# IO-shield.net
KiCad netlist of a schematic drawn in EAGLE
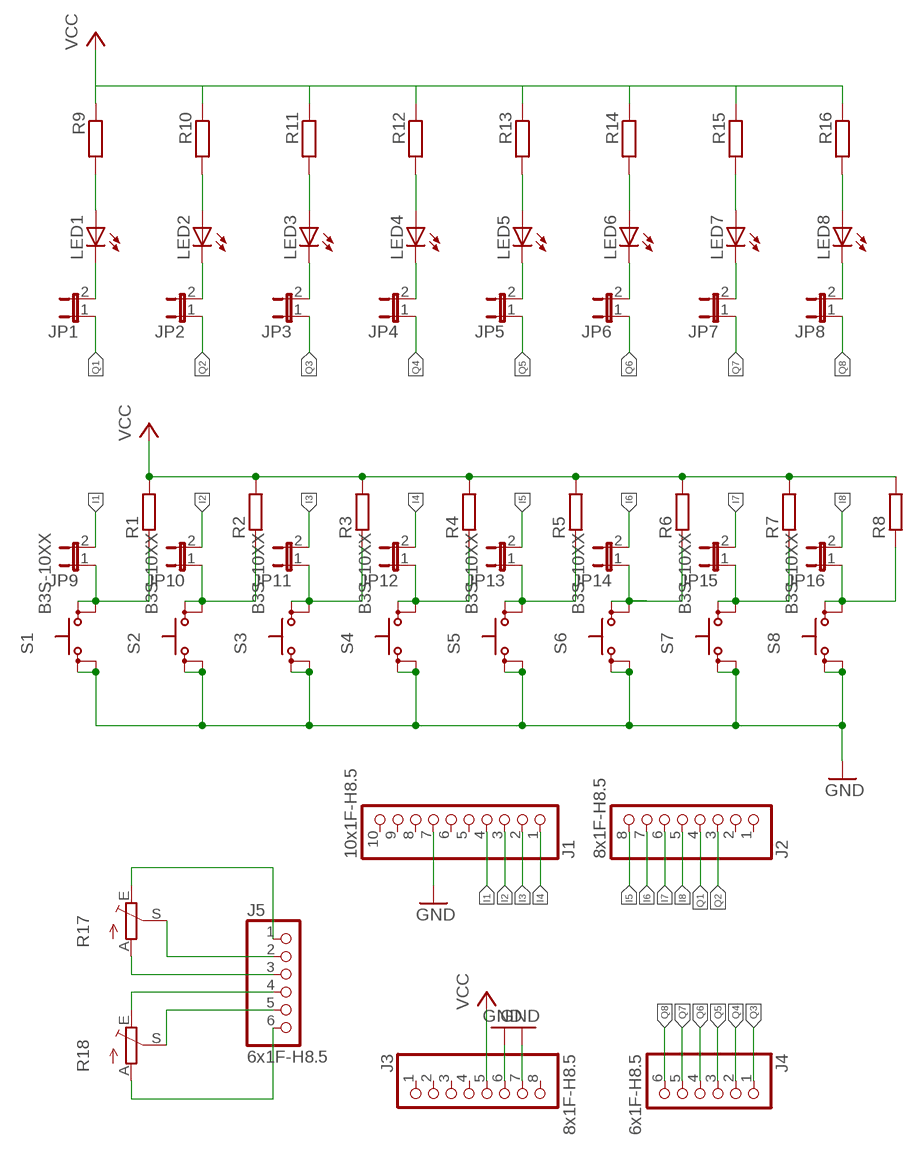
[diagram p0: schematic, sheet 1]

(export (version "E")
  (design (tool "Eeschema 10.0.6"))
  (components
    (comp (ref "J1")
      (value "10x1F-H8.5")
      (footprint "eagle-import:1X10")
      (libsource (lib "eagle-import") (part "PINHD-1X10"))
    )
    (comp (ref "J2")
      (value "8x1F-H8.5")
      (footprint "eagle-import:1X08")
      (libsource (lib "eagle-import") (part "PINHD-1X8"))
    )
    (comp (ref "J3")
      (value "8x1F-H8.5")
      (footprint "eagle-import:1X08")
      (libsource (lib "eagle-import") (part "PINHD-1X8"))
    )
    (comp (ref "J4")
      (value "6x1F-H8.5")
      (footprint "eagle-import:1X06")
      (libsource (lib "eagle-import") (part "PINHD-1X6"))
    )
    (comp (ref "J5")
      (value "6x1F-H8.5")
      (footprint "eagle-import:1X06")
      (libsource (lib "eagle-import") (part "PINHD-1X6"))
    )
    (comp (ref "JP1")
      (value "JP1E")
      (footprint "eagle-import:JP1")
      (libsource (lib "eagle-import") (part "JP1E"))
    )
    (comp (ref "JP2")
      (value "JP1E")
      (footprint "eagle-import:JP1")
      (libsource (lib "eagle-import") (part "JP1E"))
    )
    (comp (ref "JP3")
      (value "JP1E")
      (footprint "eagle-import:JP1")
      (libsource (lib "eagle-import") (part "JP1E"))
    )
    (comp (ref "JP4")
      (value "JP1E")
      (footprint "eagle-import:JP1")
      (libsource (lib "eagle-import") (part "JP1E"))
    )
    (comp (ref "JP5")
      (value "JP1E")
      (footprint "eagle-import:JP1")
      (libsource (lib "eagle-import") (part "JP1E"))
    )
    (comp (ref "JP6")
      (value "JP1E")
      (footprint "eagle-import:JP1")
      (libsource (lib "eagle-import") (part "JP1E"))
    )
    (comp (ref "JP7")
      (value "JP1E")
      (footprint "eagle-import:JP1")
      (libsource (lib "eagle-import") (part "JP1E"))
    )
    (comp (ref "JP8")
      (value "JP1E")
      (footprint "eagle-import:JP1")
      (libsource (lib "eagle-import") (part "JP1E"))
    )
    (comp (ref "JP9")
      (value "JP1E")
      (footprint "eagle-import:JP1")
      (libsource (lib "eagle-import") (part "JP1E"))
    )
    (comp (ref "JP10")
      (value "JP1E")
      (footprint "eagle-import:JP1")
      (libsource (lib "eagle-import") (part "JP1E"))
    )
    (comp (ref "JP11")
      (value "JP1E")
      (footprint "eagle-import:JP1")
      (libsource (lib "eagle-import") (part "JP1E"))
    )
    (comp (ref "JP12")
      (value "JP1E")
      (footprint "eagle-import:JP1")
      (libsource (lib "eagle-import") (part "JP1E"))
    )
    (comp (ref "JP13")
      (value "JP1E")
      (footprint "eagle-import:JP1")
      (libsource (lib "eagle-import") (part "JP1E"))
    )
    (comp (ref "JP14")
      (value "JP1E")
      (footprint "eagle-import:JP1")
      (libsource (lib "eagle-import") (part "JP1E"))
    )
    (comp (ref "JP15")
      (value "JP1E")
      (footprint "eagle-import:JP1")
      (libsource (lib "eagle-import") (part "JP1E"))
    )
    (comp (ref "JP16")
      (value "JP1E")
      (footprint "eagle-import:JP1")
      (libsource (lib "eagle-import") (part "JP1E"))
    )
    (comp (ref "LED1")
      (value "LEDKA-3528ASYC")
      (footprint "eagle-import:KA-3528ASYC")
      (libsource (lib "eagle-import") (part "LEDKA-3528ASYC"))
    )
    (comp (ref "LED2")
      (value "LEDKA-3528ASYC")
      (footprint "eagle-import:KA-3528ASYC")
      (libsource (lib "eagle-import") (part "LEDKA-3528ASYC"))
    )
    (comp (ref "LED3")
      (value "LEDKA-3528ASYC")
      (footprint "eagle-import:KA-3528ASYC")
      (libsource (lib "eagle-import") (part "LEDKA-3528ASYC"))
    )
    (comp (ref "LED4")
      (value "LEDKA-3528ASYC")
      (footprint "eagle-import:KA-3528ASYC")
      (libsource (lib "eagle-import") (part "LEDKA-3528ASYC"))
    )
    (comp (ref "LED5")
      (value "LEDKA-3528ASYC")
      (footprint "eagle-import:KA-3528ASYC")
      (libsource (lib "eagle-import") (part "LEDKA-3528ASYC"))
    )
    (comp (ref "LED6")
      (value "LEDKA-3528ASYC")
      (footprint "eagle-import:KA-3528ASYC")
      (libsource (lib "eagle-import") (part "LEDKA-3528ASYC"))
    )
    (comp (ref "LED7")
      (value "LEDKA-3528ASYC")
      (footprint "eagle-import:KA-3528ASYC")
      (libsource (lib "eagle-import") (part "LEDKA-3528ASYC"))
    )
    (comp (ref "LED8")
      (value "LEDKA-3528ASYC")
      (footprint "eagle-import:KA-3528ASYC")
      (libsource (lib "eagle-import") (part "LEDKA-3528ASYC"))
    )
    (comp (ref "R1")
      (value "R-EU_M1206")
      (footprint "eagle-import:M1206")
      (libsource (lib "eagle-import") (part "R-EU_M1206"))
    )
    (comp (ref "R2")
      (value "R-EU_M1206")
      (footprint "eagle-import:M1206")
      (libsource (lib "eagle-import") (part "R-EU_M1206"))
    )
    (comp (ref "R3")
      (value "R-EU_M1206")
      (footprint "eagle-import:M1206")
      (libsource (lib "eagle-import") (part "R-EU_M1206"))
    )
    (comp (ref "R4")
      (value "R-EU_M1206")
      (footprint "eagle-import:M1206")
      (libsource (lib "eagle-import") (part "R-EU_M1206"))
    )
    (comp (ref "R5")
      (value "R-EU_M1206")
      (footprint "eagle-import:M1206")
      (libsource (lib "eagle-import") (part "R-EU_M1206"))
    )
    (comp (ref "R6")
      (value "R-EU_M1206")
      (footprint "eagle-import:M1206")
      (libsource (lib "eagle-import") (part "R-EU_M1206"))
    )
    (comp (ref "R7")
      (value "R-EU_M1206")
      (footprint "eagle-import:M1206")
      (libsource (lib "eagle-import") (part "R-EU_M1206"))
    )
    (comp (ref "R8")
      (value "R-EU_M1206")
      (footprint "eagle-import:M1206")
      (libsource (lib "eagle-import") (part "R-EU_M1206"))
    )
    (comp (ref "R9")
      (value "R-EU_M1206")
      (footprint "eagle-import:M1206")
      (libsource (lib "eagle-import") (part "R-EU_M1206"))
    )
    (comp (ref "R10")
      (value "R-EU_M1206")
      (footprint "eagle-import:M1206")
      (libsource (lib "eagle-import") (part "R-EU_M1206"))
    )
    (comp (ref "R11")
      (value "R-EU_M1206")
      (footprint "eagle-import:M1206")
      (libsource (lib "eagle-import") (part "R-EU_M1206"))
    )
    (comp (ref "R12")
      (value "R-EU_M1206")
      (footprint "eagle-import:M1206")
      (libsource (lib "eagle-import") (part "R-EU_M1206"))
    )
    (comp (ref "R13")
      (value "R-EU_M1206")
      (footprint "eagle-import:M1206")
      (libsource (lib "eagle-import") (part "R-EU_M1206"))
    )
    (comp (ref "R14")
      (value "R-EU_M1206")
      (footprint "eagle-import:M1206")
      (libsource (lib "eagle-import") (part "R-EU_M1206"))
    )
    (comp (ref "R15")
      (value "R-EU_M1206")
      (footprint "eagle-import:M1206")
      (libsource (lib "eagle-import") (part "R-EU_M1206"))
    )
    (comp (ref "R16")
      (value "R-EU_M1206")
      (footprint "eagle-import:M1206")
      (libsource (lib "eagle-import") (part "R-EU_M1206"))
    )
    (comp (ref "R17")
      (value "TRIM_EU-CA6V")
      (footprint "eagle-import:CA6V")
      (libsource (lib "eagle-import") (part "TRIM_EU-CA6V"))
    )
    (comp (ref "R18")
      (value "TRIM_EU-CA6V")
      (footprint "eagle-import:CA6V")
      (libsource (lib "eagle-import") (part "TRIM_EU-CA6V"))
    )
    (comp (ref "S1")
      (value "B3S-10XX")
      (footprint "eagle-import:B3S-10XX")
      (libsource (lib "eagle-import") (part "B3S-10XX"))
    )
    (comp (ref "S2")
      (value "B3S-10XX")
      (footprint "eagle-import:B3S-10XX")
      (libsource (lib "eagle-import") (part "B3S-10XX"))
    )
    (comp (ref "S3")
      (value "B3S-10XX")
      (footprint "eagle-import:B3S-10XX")
      (libsource (lib "eagle-import") (part "B3S-10XX"))
    )
    (comp (ref "S4")
      (value "B3S-10XX")
      (footprint "eagle-import:B3S-10XX")
      (libsource (lib "eagle-import") (part "B3S-10XX"))
    )
    (comp (ref "S5")
      (value "B3S-10XX")
      (footprint "eagle-import:B3S-10XX")
      (libsource (lib "eagle-import") (part "B3S-10XX"))
    )
    (comp (ref "S6")
      (value "B3S-10XX")
      (footprint "eagle-import:B3S-10XX")
      (libsource (lib "eagle-import") (part "B3S-10XX"))
    )
    (comp (ref "S7")
      (value "B3S-10XX")
      (footprint "eagle-import:B3S-10XX")
      (libsource (lib "eagle-import") (part "B3S-10XX"))
    )
    (comp (ref "S8")
      (value "B3S-10XX")
      (footprint "eagle-import:B3S-10XX")
      (libsource (lib "eagle-import") (part "B3S-10XX"))
    )
  )
  (nets
    (net (code "1") (name "GND") (class "Default")
      (node (ref "J1") (pin "7") (pinfunction "7_7") (pintype "passive"))
      (node (ref "J3") (pin "6") (pinfunction "6_6") (pintype "passive"))
      (node (ref "J3") (pin "7") (pinfunction "7_7") (pintype "passive"))
      (node (ref "S1") (pin "1") (pinfunction "P_1") (pintype "passive"))
      (node (ref "S1") (pin "2") (pinfunction "P1_2") (pintype "passive"))
      (node (ref "S2") (pin "1") (pinfunction "P_1") (pintype "passive"))
      (node (ref "S2") (pin "2") (pinfunction "P1_2") (pintype "passive"))
      (node (ref "S3") (pin "1") (pinfunction "P_1") (pintype "passive"))
      (node (ref "S3") (pin "2") (pinfunction "P1_2") (pintype "passive"))
      (node (ref "S4") (pin "1") (pinfunction "P_1") (pintype "passive"))
      (node (ref "S4") (pin "2") (pinfunction "P1_2") (pintype "passive"))
      (node (ref "S5") (pin "1") (pinfunction "P_1") (pintype "passive"))
      (node (ref "S5") (pin "2") (pinfunction "P1_2") (pintype "passive"))
      (node (ref "S6") (pin "1") (pinfunction "P_1") (pintype "passive"))
      (node (ref "S6") (pin "2") (pinfunction "P1_2") (pintype "passive"))
      (node (ref "S7") (pin "1") (pinfunction "P_1") (pintype "passive"))
      (node (ref "S7") (pin "2") (pinfunction "P1_2") (pintype "passive"))
      (node (ref "S8") (pin "1") (pinfunction "P_1") (pintype "passive"))
      (node (ref "S8") (pin "2") (pinfunction "P1_2") (pintype "passive"))
    )
    (net (code "2") (name "I1") (class "Default")
      (node (ref "J1") (pin "4") (pinfunction "4_4") (pintype "passive"))
      (node (ref "JP9") (pin "2") (pinfunction "2_2") (pintype "passive"))
    )
    (net (code "3") (name "I2") (class "Default")
      (node (ref "J1") (pin "3") (pinfunction "3_3") (pintype "passive"))
      (node (ref "JP10") (pin "2") (pinfunction "2_2") (pintype "passive"))
    )
    (net (code "4") (name "I3") (class "Default")
      (node (ref "J1") (pin "2") (pinfunction "2_2") (pintype "passive"))
      (node (ref "JP11") (pin "2") (pinfunction "2_2") (pintype "passive"))
    )
    (net (code "5") (name "I4") (class "Default")
      (node (ref "J1") (pin "1") (pinfunction "1_1") (pintype "passive"))
      (node (ref "JP12") (pin "2") (pinfunction "2_2") (pintype "passive"))
    )
    (net (code "6") (name "I5") (class "Default")
      (node (ref "J2") (pin "8") (pinfunction "8_8") (pintype "passive"))
      (node (ref "JP13") (pin "2") (pinfunction "2_2") (pintype "passive"))
    )
    (net (code "7") (name "I6") (class "Default")
      (node (ref "J2") (pin "7") (pinfunction "7_7") (pintype "passive"))
      (node (ref "JP14") (pin "2") (pinfunction "2_2") (pintype "passive"))
    )
    (net (code "8") (name "I7") (class "Default")
      (node (ref "J2") (pin "6") (pinfunction "6_6") (pintype "passive"))
      (node (ref "JP15") (pin "2") (pinfunction "2_2") (pintype "passive"))
    )
    (net (code "9") (name "I8") (class "Default")
      (node (ref "J2") (pin "5") (pinfunction "5_5") (pintype "passive"))
      (node (ref "JP16") (pin "2") (pinfunction "2_2") (pintype "passive"))
    )
    (net (code "10") (name "Net-(J5-Pad1)") (class "Default")
      (node (ref "J5") (pin "1") (pinfunction "1_1") (pintype "passive"))
      (node (ref "R17") (pin "E") (pinfunction "E_E") (pintype "passive"))
    )
    (net (code "11") (name "Net-(J5-Pad2)") (class "Default")
      (node (ref "J5") (pin "2") (pinfunction "2_2") (pintype "passive"))
      (node (ref "R17") (pin "S") (pinfunction "S_S") (pintype "passive"))
    )
    (net (code "12") (name "Net-(J5-Pad3)") (class "Default")
      (node (ref "J5") (pin "3") (pinfunction "3_3") (pintype "passive"))
      (node (ref "R17") (pin "A") (pinfunction "A_A") (pintype "passive"))
    )
    (net (code "13") (name "Net-(J5-Pad4)") (class "Default")
      (node (ref "J5") (pin "4") (pinfunction "4_4") (pintype "passive"))
      (node (ref "R18") (pin "E") (pinfunction "E_E") (pintype "passive"))
    )
    (net (code "14") (name "Net-(J5-Pad5)") (class "Default")
      (node (ref "J5") (pin "5") (pinfunction "5_5") (pintype "passive"))
      (node (ref "R18") (pin "S") (pinfunction "S_S") (pintype "passive"))
    )
    (net (code "15") (name "Net-(J5-Pad6)") (class "Default")
      (node (ref "J5") (pin "6") (pinfunction "6_6") (pintype "passive"))
      (node (ref "R18") (pin "A") (pinfunction "A_A") (pintype "passive"))
    )
    (net (code "16") (name "Net-(JP1-Pad2)") (class "Default")
      (node (ref "JP1") (pin "2") (pinfunction "2_2") (pintype "passive"))
      (node (ref "LED1") (pin "C") (pinfunction "C_C") (pintype "passive"))
    )
    (net (code "17") (name "Net-(JP2-Pad2)") (class "Default")
      (node (ref "JP2") (pin "2") (pinfunction "2_2") (pintype "passive"))
      (node (ref "LED2") (pin "C") (pinfunction "C_C") (pintype "passive"))
    )
    (net (code "18") (name "Net-(JP3-Pad2)") (class "Default")
      (node (ref "JP3") (pin "2") (pinfunction "2_2") (pintype "passive"))
      (node (ref "LED3") (pin "C") (pinfunction "C_C") (pintype "passive"))
    )
    (net (code "19") (name "Net-(JP4-Pad2)") (class "Default")
      (node (ref "JP4") (pin "2") (pinfunction "2_2") (pintype "passive"))
      (node (ref "LED4") (pin "C") (pinfunction "C_C") (pintype "passive"))
    )
    (net (code "20") (name "Net-(JP5-Pad2)") (class "Default")
      (node (ref "JP5") (pin "2") (pinfunction "2_2") (pintype "passive"))
      (node (ref "LED5") (pin "C") (pinfunction "C_C") (pintype "passive"))
    )
    (net (code "21") (name "Net-(JP6-Pad2)") (class "Default")
      (node (ref "JP6") (pin "2") (pinfunction "2_2") (pintype "passive"))
      (node (ref "LED6") (pin "C") (pinfunction "C_C") (pintype "passive"))
    )
    (net (code "22") (name "Net-(JP7-Pad2)") (class "Default")
      (node (ref "JP7") (pin "2") (pinfunction "2_2") (pintype "passive"))
      (node (ref "LED7") (pin "C") (pinfunction "C_C") (pintype "passive"))
    )
    (net (code "23") (name "Net-(JP8-Pad2)") (class "Default")
      (node (ref "JP8") (pin "2") (pinfunction "2_2") (pintype "passive"))
      (node (ref "LED8") (pin "C") (pinfunction "C_C") (pintype "passive"))
    )
    (net (code "24") (name "Net-(LED1-PadA)") (class "Default")
      (node (ref "LED1") (pin "A") (pinfunction "A_A") (pintype "passive"))
      (node (ref "R9") (pin "2") (pinfunction "2_2") (pintype "passive"))
    )
    (net (code "25") (name "Net-(LED2-PadA)") (class "Default")
      (node (ref "LED2") (pin "A") (pinfunction "A_A") (pintype "passive"))
      (node (ref "R10") (pin "2") (pinfunction "2_2") (pintype "passive"))
    )
    (net (code "26") (name "Net-(LED3-PadA)") (class "Default")
      (node (ref "LED3") (pin "A") (pinfunction "A_A") (pintype "passive"))
      (node (ref "R11") (pin "2") (pinfunction "2_2") (pintype "passive"))
    )
    (net (code "27") (name "Net-(LED4-PadA)") (class "Default")
      (node (ref "LED4") (pin "A") (pinfunction "A_A") (pintype "passive"))
      (node (ref "R12") (pin "2") (pinfunction "2_2") (pintype "passive"))
    )
    (net (code "28") (name "Net-(LED5-PadA)") (class "Default")
      (node (ref "LED5") (pin "A") (pinfunction "A_A") (pintype "passive"))
      (node (ref "R13") (pin "2") (pinfunction "2_2") (pintype "passive"))
    )
    (net (code "29") (name "Net-(LED6-PadA)") (class "Default")
      (node (ref "LED6") (pin "A") (pinfunction "A_A") (pintype "passive"))
      (node (ref "R14") (pin "2") (pinfunction "2_2") (pintype "passive"))
    )
    (net (code "30") (name "Net-(LED7-PadA)") (class "Default")
      (node (ref "LED7") (pin "A") (pinfunction "A_A") (pintype "passive"))
      (node (ref "R15") (pin "2") (pinfunction "2_2") (pintype "passive"))
    )
    (net (code "31") (name "Net-(LED8-PadA)") (class "Default")
      (node (ref "LED8") (pin "A") (pinfunction "A_A") (pintype "passive"))
      (node (ref "R16") (pin "2") (pinfunction "2_2") (pintype "passive"))
    )
    (net (code "32") (name "Net-(S1-S)") (class "Default")
      (node (ref "JP9") (pin "1") (pinfunction "1_1") (pintype "passive"))
      (node (ref "R1") (pin "1") (pinfunction "1_1") (pintype "passive"))
      (node (ref "S1") (pin "3") (pinfunction "S_3") (pintype "passive"))
      (node (ref "S1") (pin "4") (pinfunction "S1_4") (pintype "passive"))
    )
    (net (code "33") (name "Net-(S2-S)") (class "Default")
      (node (ref "JP10") (pin "1") (pinfunction "1_1") (pintype "passive"))
      (node (ref "R2") (pin "1") (pinfunction "1_1") (pintype "passive"))
      (node (ref "S2") (pin "3") (pinfunction "S_3") (pintype "passive"))
      (node (ref "S2") (pin "4") (pinfunction "S1_4") (pintype "passive"))
    )
    (net (code "34") (name "Net-(S3-S)") (class "Default")
      (node (ref "JP11") (pin "1") (pinfunction "1_1") (pintype "passive"))
      (node (ref "R3") (pin "1") (pinfunction "1_1") (pintype "passive"))
      (node (ref "S3") (pin "3") (pinfunction "S_3") (pintype "passive"))
      (node (ref "S3") (pin "4") (pinfunction "S1_4") (pintype "passive"))
    )
    (net (code "35") (name "Net-(S4-S)") (class "Default")
      (node (ref "JP12") (pin "1") (pinfunction "1_1") (pintype "passive"))
      (node (ref "R4") (pin "1") (pinfunction "1_1") (pintype "passive"))
      (node (ref "S4") (pin "3") (pinfunction "S_3") (pintype "passive"))
      (node (ref "S4") (pin "4") (pinfunction "S1_4") (pintype "passive"))
    )
    (net (code "36") (name "Net-(S5-S)") (class "Default")
      (node (ref "JP13") (pin "1") (pinfunction "1_1") (pintype "passive"))
      (node (ref "R5") (pin "1") (pinfunction "1_1") (pintype "passive"))
      (node (ref "S5") (pin "3") (pinfunction "S_3") (pintype "passive"))
      (node (ref "S5") (pin "4") (pinfunction "S1_4") (pintype "passive"))
    )
    (net (code "37") (name "Net-(S6-S)") (class "Default")
      (node (ref "JP14") (pin "1") (pinfunction "1_1") (pintype "passive"))
      (node (ref "R6") (pin "1") (pinfunction "1_1") (pintype "passive"))
      (node (ref "S6") (pin "3") (pinfunction "S_3") (pintype "passive"))
      (node (ref "S6") (pin "4") (pinfunction "S1_4") (pintype "passive"))
    )
    (net (code "38") (name "Net-(S7-S)") (class "Default")
      (node (ref "JP15") (pin "1") (pinfunction "1_1") (pintype "passive"))
      (node (ref "R7") (pin "1") (pinfunction "1_1") (pintype "passive"))
      (node (ref "S7") (pin "3") (pinfunction "S_3") (pintype "passive"))
      (node (ref "S7") (pin "4") (pinfunction "S1_4") (pintype "passive"))
    )
    (net (code "39") (name "Net-(S8-S)") (class "Default")
      (node (ref "JP16") (pin "1") (pinfunction "1_1") (pintype "passive"))
      (node (ref "R8") (pin "1") (pinfunction "1_1") (pintype "passive"))
      (node (ref "S8") (pin "3") (pinfunction "S_3") (pintype "passive"))
      (node (ref "S8") (pin "4") (pinfunction "S1_4") (pintype "passive"))
    )
    (net (code "40") (name "Q1") (class "Default")
      (node (ref "J2") (pin "4") (pinfunction "4_4") (pintype "passive"))
      (node (ref "JP1") (pin "1") (pinfunction "1_1") (pintype "passive"))
    )
    (net (code "41") (name "Q2") (class "Default")
      (node (ref "J2") (pin "3") (pinfunction "3_3") (pintype "passive"))
      (node (ref "JP2") (pin "1") (pinfunction "1_1") (pintype "passive"))
    )
    (net (code "42") (name "Q3") (class "Default")
      (node (ref "J4") (pin "1") (pinfunction "1_1") (pintype "passive"))
      (node (ref "JP3") (pin "1") (pinfunction "1_1") (pintype "passive"))
    )
    (net (code "43") (name "Q4") (class "Default")
      (node (ref "J4") (pin "2") (pinfunction "2_2") (pintype "passive"))
      (node (ref "JP4") (pin "1") (pinfunction "1_1") (pintype "passive"))
    )
    (net (code "44") (name "Q5") (class "Default")
      (node (ref "J4") (pin "3") (pinfunction "3_3") (pintype "passive"))
      (node (ref "JP5") (pin "1") (pinfunction "1_1") (pintype "passive"))
    )
    (net (code "45") (name "Q6") (class "Default")
      (node (ref "J4") (pin "4") (pinfunction "4_4") (pintype "passive"))
      (node (ref "JP6") (pin "1") (pinfunction "1_1") (pintype "passive"))
    )
    (net (code "46") (name "Q7") (class "Default")
      (node (ref "J4") (pin "5") (pinfunction "5_5") (pintype "passive"))
      (node (ref "JP7") (pin "1") (pinfunction "1_1") (pintype "passive"))
    )
    (net (code "47") (name "Q8") (class "Default")
      (node (ref "J4") (pin "6") (pinfunction "6_6") (pintype "passive"))
      (node (ref "JP8") (pin "1") (pinfunction "1_1") (pintype "passive"))
    )
    (net (code "48") (name "VCC") (class "Default")
      (node (ref "J3") (pin "5") (pinfunction "5_5") (pintype "passive"))
      (node (ref "R1") (pin "2") (pinfunction "2_2") (pintype "passive"))
      (node (ref "R10") (pin "1") (pinfunction "1_1") (pintype "passive"))
      (node (ref "R11") (pin "1") (pinfunction "1_1") (pintype "passive"))
      (node (ref "R12") (pin "1") (pinfunction "1_1") (pintype "passive"))
      (node (ref "R13") (pin "1") (pinfunction "1_1") (pintype "passive"))
      (node (ref "R14") (pin "1") (pinfunction "1_1") (pintype "passive"))
      (node (ref "R15") (pin "1") (pinfunction "1_1") (pintype "passive"))
      (node (ref "R16") (pin "1") (pinfunction "1_1") (pintype "passive"))
      (node (ref "R2") (pin "2") (pinfunction "2_2") (pintype "passive"))
      (node (ref "R3") (pin "2") (pinfunction "2_2") (pintype "passive"))
      (node (ref "R4") (pin "2") (pinfunction "2_2") (pintype "passive"))
      (node (ref "R5") (pin "2") (pinfunction "2_2") (pintype "passive"))
      (node (ref "R6") (pin "2") (pinfunction "2_2") (pintype "passive"))
      (node (ref "R7") (pin "2") (pinfunction "2_2") (pintype "passive"))
      (node (ref "R8") (pin "2") (pinfunction "2_2") (pintype "passive"))
      (node (ref "R9") (pin "1") (pinfunction "1_1") (pintype "passive"))
    )
    (net (code "49") (name "unconnected-(J1-Pad5)") (class "Default")
      (node (ref "J1") (pin "5") (pinfunction "5_5") (pintype "passive"))
    )
    (net (code "50") (name "unconnected-(J1-Pad6)") (class "Default")
      (node (ref "J1") (pin "6") (pinfunction "6_6") (pintype "passive"))
    )
    (net (code "51") (name "unconnected-(J1-Pad8)") (class "Default")
      (node (ref "J1") (pin "8") (pinfunction "8_8") (pintype "passive"))
    )
    (net (code "52") (name "unconnected-(J1-Pad9)") (class "Default")
      (node (ref "J1") (pin "9") (pinfunction "9_9") (pintype "passive"))
    )
    (net (code "53") (name "unconnected-(J1-Pad10)") (class "Default")
      (node (ref "J1") (pin "10") (pinfunction "10_10") (pintype "passive"))
    )
    (net (code "54") (name "unconnected-(J2-Pad1)") (class "Default")
      (node (ref "J2") (pin "1") (pinfunction "1_1") (pintype "passive"))
    )
    (net (code "55") (name "unconnected-(J2-Pad2)") (class "Default")
      (node (ref "J2") (pin "2") (pinfunction "2_2") (pintype "passive"))
    )
    (net (code "56") (name "unconnected-(J3-Pad1)") (class "Default")
      (node (ref "J3") (pin "1") (pinfunction "1_1") (pintype "passive"))
    )
    (net (code "57") (name "unconnected-(J3-Pad2)") (class "Default")
      (node (ref "J3") (pin "2") (pinfunction "2_2") (pintype "passive"))
    )
    (net (code "58") (name "unconnected-(J3-Pad3)") (class "Default")
      (node (ref "J3") (pin "3") (pinfunction "3_3") (pintype "passive"))
    )
    (net (code "59") (name "unconnected-(J3-Pad4)") (class "Default")
      (node (ref "J3") (pin "4") (pinfunction "4_4") (pintype "passive"))
    )
    (net (code "60") (name "unconnected-(J3-Pad8)") (class "Default")
      (node (ref "J3") (pin "8") (pinfunction "8_8") (pintype "passive"))
    )
  )
)
